# pulse_generator.net
KiCad netlist of a schematic drawn in EAGLE
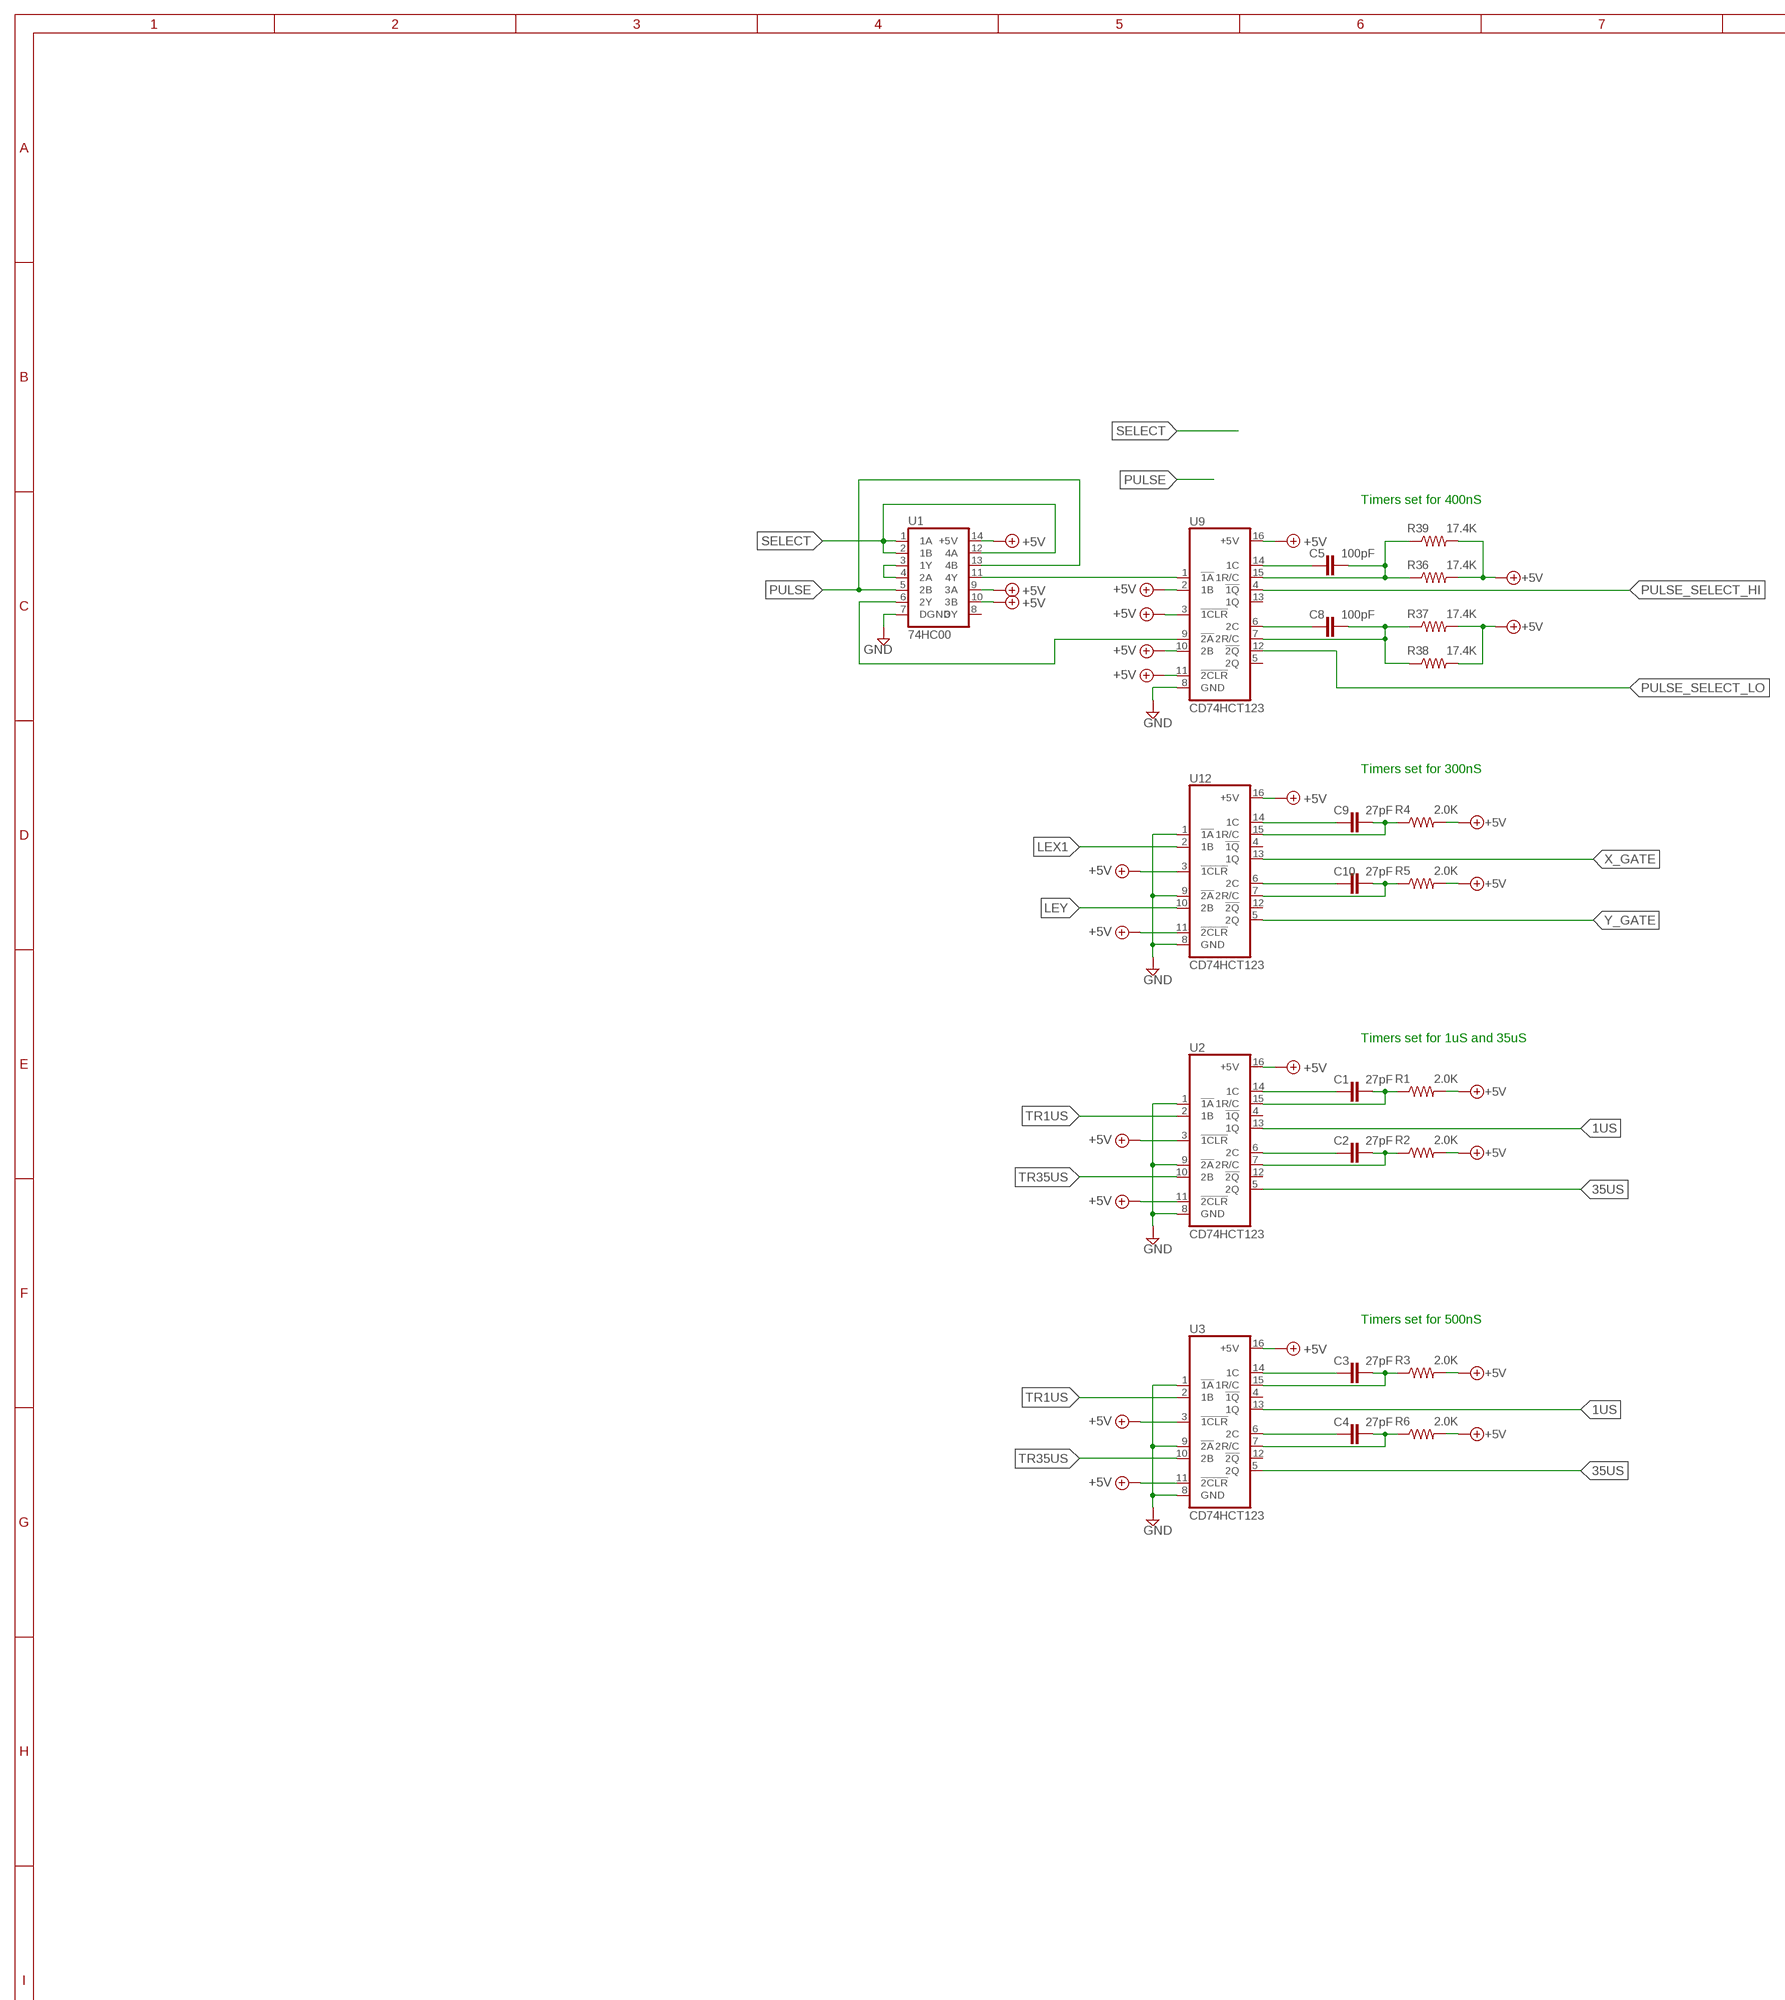
[diagram p0: schematic, sheet 1, part 1 of 2]
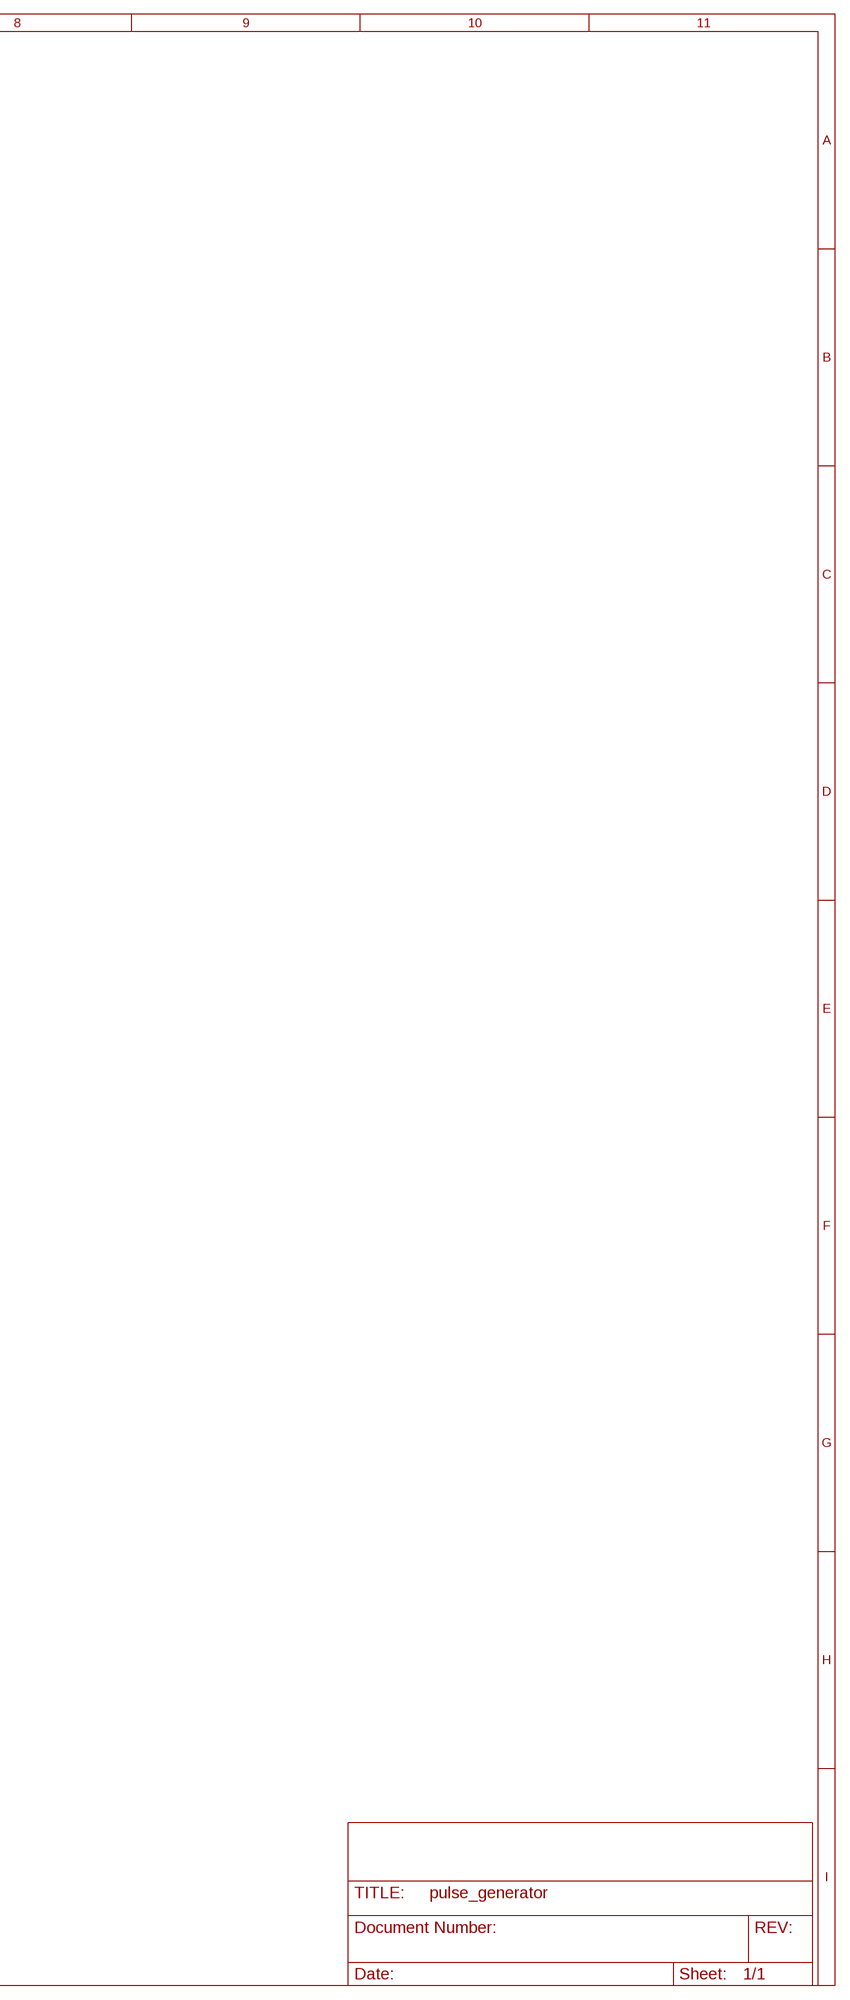
[diagram p1: schematic, sheet 1, part 2 of 2]

(export (version "E")
  (design (tool "Eeschema 10.0.6"))
  (components
    (comp (ref "C1")
      (value "27pF")
      (footprint "eagle-import:C2.5")
      (libsource (lib "eagle-import") (part "C-0.1"))
    )
    (comp (ref "C2")
      (value "27pF")
      (footprint "eagle-import:C2.5")
      (libsource (lib "eagle-import") (part "C-0.1"))
    )
    (comp (ref "C3")
      (value "27pF")
      (footprint "eagle-import:C2.5")
      (libsource (lib "eagle-import") (part "C-0.1"))
    )
    (comp (ref "C4")
      (value "27pF")
      (footprint "eagle-import:C2.5")
      (libsource (lib "eagle-import") (part "C-0.1"))
    )
    (comp (ref "C5")
      (value "100pF")
      (footprint "eagle-import:C2.5")
      (libsource (lib "eagle-import") (part "C-0.1"))
    )
    (comp (ref "C8")
      (value "100pF")
      (footprint "eagle-import:C2.5")
      (libsource (lib "eagle-import") (part "C-0.1"))
    )
    (comp (ref "C9")
      (value "27pF")
      (footprint "eagle-import:C2.5")
      (libsource (lib "eagle-import") (part "C-0.1"))
    )
    (comp (ref "C10")
      (value "27pF")
      (footprint "eagle-import:C2.5")
      (libsource (lib "eagle-import") (part "C-0.1"))
    )
    (comp (ref "R1")
      (value "2.0K")
      (footprint "eagle-import:0207_10")
      (libsource (lib "eagle-import") (part "R-1/4WATT"))
    )
    (comp (ref "R2")
      (value "2.0K")
      (footprint "eagle-import:0207_10")
      (libsource (lib "eagle-import") (part "R-1/4WATT"))
    )
    (comp (ref "R3")
      (value "2.0K")
      (footprint "eagle-import:0207_10")
      (libsource (lib "eagle-import") (part "R-1/4WATT"))
    )
    (comp (ref "R4")
      (value "2.0K")
      (footprint "eagle-import:0207_10")
      (libsource (lib "eagle-import") (part "R-1/4WATT"))
    )
    (comp (ref "R5")
      (value "2.0K")
      (footprint "eagle-import:0207_10")
      (libsource (lib "eagle-import") (part "R-1/4WATT"))
    )
    (comp (ref "R6")
      (value "2.0K")
      (footprint "eagle-import:0207_10")
      (libsource (lib "eagle-import") (part "R-1/4WATT"))
    )
    (comp (ref "R36")
      (value "17.4K")
      (footprint "eagle-import:0207_10")
      (libsource (lib "eagle-import") (part "R-1/4WATT"))
    )
    (comp (ref "R37")
      (value "17.4K")
      (footprint "eagle-import:0207_10")
      (libsource (lib "eagle-import") (part "R-1/4WATT"))
    )
    (comp (ref "R38")
      (value "17.4K")
      (footprint "eagle-import:0207_10")
      (libsource (lib "eagle-import") (part "R-1/4WATT"))
    )
    (comp (ref "R39")
      (value "17.4K")
      (footprint "eagle-import:0207_10")
      (libsource (lib "eagle-import") (part "R-1/4WATT"))
    )
    (comp (ref "U1")
      (value "74HC00")
      (footprint "eagle-import:DIP-14")
      (libsource (lib "eagle-import") (part "CD74HC00"))
    )
    (comp (ref "U2")
      (value "CD74HCT123")
      (footprint "eagle-import:DIP-16")
      (libsource (lib "eagle-import") (part "CD74HCT123"))
    )
    (comp (ref "U3")
      (value "CD74HCT123")
      (footprint "eagle-import:DIP-16")
      (libsource (lib "eagle-import") (part "CD74HCT123"))
    )
    (comp (ref "U9")
      (value "CD74HCT123")
      (footprint "eagle-import:DIP-16")
      (libsource (lib "eagle-import") (part "CD74HCT123"))
    )
    (comp (ref "U12")
      (value "CD74HCT123")
      (footprint "eagle-import:DIP-16")
      (libsource (lib "eagle-import") (part "CD74HCT123"))
    )
  )
  (nets
    (net (code "1") (name "+5V") (class "Default")
      (node (ref "R1") (pin "2") (pinfunction "P$2_2") (pintype "passive"))
      (node (ref "R2") (pin "2") (pinfunction "P$2_2") (pintype "passive"))
      (node (ref "R3") (pin "2") (pinfunction "P$2_2") (pintype "passive"))
      (node (ref "R36") (pin "2") (pinfunction "P$2_2") (pintype "passive"))
      (node (ref "R37") (pin "2") (pinfunction "P$2_2") (pintype "passive"))
      (node (ref "R38") (pin "2") (pinfunction "P$2_2") (pintype "passive"))
      (node (ref "R39") (pin "2") (pinfunction "P$2_2") (pintype "passive"))
      (node (ref "R4") (pin "2") (pinfunction "P$2_2") (pintype "passive"))
      (node (ref "R5") (pin "2") (pinfunction "P$2_2") (pintype "passive"))
      (node (ref "R6") (pin "2") (pinfunction "P$2_2") (pintype "passive"))
      (node (ref "U1") (pin "10") (pinfunction "3B_10") (pintype "input"))
      (node (ref "U1") (pin "14") (pinfunction "+5V_14") (pintype "power_in"))
      (node (ref "U1") (pin "9") (pinfunction "3A_9") (pintype "input"))
      (node (ref "U12") (pin "11") (pinfunction "~{2CLR}_11") (pintype "input"))
      (node (ref "U12") (pin "16") (pinfunction "+5V_16") (pintype "power_in"))
      (node (ref "U12") (pin "3") (pinfunction "~{1CLR}_3") (pintype "input"))
      (node (ref "U2") (pin "11") (pinfunction "~{2CLR}_11") (pintype "input"))
      (node (ref "U2") (pin "16") (pinfunction "+5V_16") (pintype "power_in"))
      (node (ref "U2") (pin "3") (pinfunction "~{1CLR}_3") (pintype "input"))
      (node (ref "U3") (pin "11") (pinfunction "~{2CLR}_11") (pintype "input"))
      (node (ref "U3") (pin "16") (pinfunction "+5V_16") (pintype "power_in"))
      (node (ref "U3") (pin "3") (pinfunction "~{1CLR}_3") (pintype "input"))
      (node (ref "U9") (pin "10") (pinfunction "2B_10") (pintype "input"))
      (node (ref "U9") (pin "11") (pinfunction "~{2CLR}_11") (pintype "input"))
      (node (ref "U9") (pin "16") (pinfunction "+5V_16") (pintype "power_in"))
      (node (ref "U9") (pin "2") (pinfunction "1B_2") (pintype "input"))
      (node (ref "U9") (pin "3") (pinfunction "~{1CLR}_3") (pintype "input"))
    )
    (net (code "2") (name "1US") (class "Default")
      (node (ref "U2") (pin "13") (pinfunction "1Q_13") (pintype "output"))
      (node (ref "U3") (pin "13") (pinfunction "1Q_13") (pintype "output"))
    )
    (net (code "3") (name "35US") (class "Default")
      (node (ref "U2") (pin "5") (pinfunction "2Q_5") (pintype "output"))
      (node (ref "U3") (pin "5") (pinfunction "2Q_5") (pintype "output"))
    )
    (net (code "4") (name "GND") (class "Default")
      (node (ref "U1") (pin "7") (pinfunction "DGND_7") (pintype "power_in"))
      (node (ref "U12") (pin "1") (pinfunction "~{1A}_1") (pintype "input"))
      (node (ref "U12") (pin "8") (pinfunction "GND_8") (pintype "power_in"))
      (node (ref "U12") (pin "9") (pinfunction "~{2A}_9") (pintype "input"))
      (node (ref "U2") (pin "1") (pinfunction "~{1A}_1") (pintype "input"))
      (node (ref "U2") (pin "8") (pinfunction "GND_8") (pintype "power_in"))
      (node (ref "U2") (pin "9") (pinfunction "~{2A}_9") (pintype "input"))
      (node (ref "U3") (pin "1") (pinfunction "~{1A}_1") (pintype "input"))
      (node (ref "U3") (pin "8") (pinfunction "GND_8") (pintype "power_in"))
      (node (ref "U3") (pin "9") (pinfunction "~{2A}_9") (pintype "input"))
      (node (ref "U9") (pin "8") (pinfunction "GND_8") (pintype "power_in"))
    )
    (net (code "5") (name "LEX1") (class "Default")
      (node (ref "U12") (pin "2") (pinfunction "1B_2") (pintype "input"))
    )
    (net (code "7") (name "Net-(R1-P$1)") (class "Default")
      (node (ref "C1") (pin "2") (pinfunction "2_2") (pintype "passive"))
      (node (ref "R1") (pin "1") (pinfunction "P$1_1") (pintype "passive"))
      (node (ref "U2") (pin "15") (pinfunction "1R/C_15") (pintype "passive"))
    )
    (net (code "8") (name "Net-(R2-P$1)") (class "Default")
      (node (ref "C2") (pin "2") (pinfunction "2_2") (pintype "passive"))
      (node (ref "R2") (pin "1") (pinfunction "P$1_1") (pintype "passive"))
      (node (ref "U2") (pin "7") (pinfunction "2R/C_7") (pintype "passive"))
    )
    (net (code "9") (name "Net-(R3-P$1)") (class "Default")
      (node (ref "C3") (pin "2") (pinfunction "2_2") (pintype "passive"))
      (node (ref "R3") (pin "1") (pinfunction "P$1_1") (pintype "passive"))
      (node (ref "U3") (pin "15") (pinfunction "1R/C_15") (pintype "passive"))
    )
    (net (code "10") (name "Net-(R4-P$1)") (class "Default")
      (node (ref "C9") (pin "2") (pinfunction "2_2") (pintype "passive"))
      (node (ref "R4") (pin "1") (pinfunction "P$1_1") (pintype "passive"))
      (node (ref "U12") (pin "15") (pinfunction "1R/C_15") (pintype "passive"))
    )
    (net (code "11") (name "Net-(R5-P$1)") (class "Default")
      (node (ref "C10") (pin "2") (pinfunction "2_2") (pintype "passive"))
      (node (ref "R5") (pin "1") (pinfunction "P$1_1") (pintype "passive"))
      (node (ref "U12") (pin "7") (pinfunction "2R/C_7") (pintype "passive"))
    )
    (net (code "12") (name "Net-(R6-P$1)") (class "Default")
      (node (ref "C4") (pin "2") (pinfunction "2_2") (pintype "passive"))
      (node (ref "R6") (pin "1") (pinfunction "P$1_1") (pintype "passive"))
      (node (ref "U3") (pin "7") (pinfunction "2R/C_7") (pintype "passive"))
    )
    (net (code "13") (name "Net-(R36-P$1)") (class "Default")
      (node (ref "C5") (pin "2") (pinfunction "2_2") (pintype "passive"))
      (node (ref "R36") (pin "1") (pinfunction "P$1_1") (pintype "passive"))
      (node (ref "R39") (pin "1") (pinfunction "P$1_1") (pintype "passive"))
      (node (ref "U9") (pin "15") (pinfunction "1R/C_15") (pintype "passive"))
    )
    (net (code "14") (name "Net-(R37-P$1)") (class "Default")
      (node (ref "C8") (pin "2") (pinfunction "2_2") (pintype "passive"))
      (node (ref "R37") (pin "1") (pinfunction "P$1_1") (pintype "passive"))
      (node (ref "R38") (pin "1") (pinfunction "P$1_1") (pintype "passive"))
      (node (ref "U9") (pin "7") (pinfunction "2R/C_7") (pintype "passive"))
    )
    (net (code "15") (name "Net-(U1-1Y)") (class "Default")
      (node (ref "U1") (pin "3") (pinfunction "1Y_3") (pintype "output"))
      (node (ref "U1") (pin "4") (pinfunction "2A_4") (pintype "input"))
    )
    (net (code "16") (name "Net-(U1-2Y)") (class "Default")
      (node (ref "U1") (pin "6") (pinfunction "2Y_6") (pintype "output"))
      (node (ref "U9") (pin "9") (pinfunction "~{2A}_9") (pintype "input"))
    )
    (net (code "17") (name "Net-(U1-4Y)") (class "Default")
      (node (ref "U1") (pin "11") (pinfunction "4Y_11") (pintype "output"))
      (node (ref "U9") (pin "1") (pinfunction "~{1A}_1") (pintype "input"))
    )
    (net (code "18") (name "Net-(U2-1C)") (class "Default")
      (node (ref "C1") (pin "1") (pinfunction "1_1") (pintype "passive"))
      (node (ref "U2") (pin "14") (pinfunction "1C_14") (pintype "passive"))
    )
    (net (code "19") (name "Net-(U2-2C)") (class "Default")
      (node (ref "C2") (pin "1") (pinfunction "1_1") (pintype "passive"))
      (node (ref "U2") (pin "6") (pinfunction "2C_6") (pintype "passive"))
    )
    (net (code "20") (name "Net-(U3-1C)") (class "Default")
      (node (ref "C3") (pin "1") (pinfunction "1_1") (pintype "passive"))
      (node (ref "U3") (pin "14") (pinfunction "1C_14") (pintype "passive"))
    )
    (net (code "21") (name "Net-(U3-2C)") (class "Default")
      (node (ref "C4") (pin "1") (pinfunction "1_1") (pintype "passive"))
      (node (ref "U3") (pin "6") (pinfunction "2C_6") (pintype "passive"))
    )
    (net (code "22") (name "Net-(U9-1C)") (class "Default")
      (node (ref "C5") (pin "1") (pinfunction "1_1") (pintype "passive"))
      (node (ref "U9") (pin "14") (pinfunction "1C_14") (pintype "passive"))
    )
    (net (code "23") (name "Net-(U9-2C)") (class "Default")
      (node (ref "C8") (pin "1") (pinfunction "1_1") (pintype "passive"))
      (node (ref "U9") (pin "6") (pinfunction "2C_6") (pintype "passive"))
    )
    (net (code "24") (name "Net-(U12-1C)") (class "Default")
      (node (ref "C9") (pin "1") (pinfunction "1_1") (pintype "passive"))
      (node (ref "U12") (pin "14") (pinfunction "1C_14") (pintype "passive"))
    )
    (net (code "25") (name "Net-(U12-2C)") (class "Default")
      (node (ref "C10") (pin "1") (pinfunction "1_1") (pintype "passive"))
      (node (ref "U12") (pin "6") (pinfunction "2C_6") (pintype "passive"))
    )
    (net (code "26") (name "PULSE") (class "Default")
      (node (ref "U1") (pin "13") (pinfunction "4B_13") (pintype "input"))
      (node (ref "U1") (pin "5") (pinfunction "2B_5") (pintype "input"))
    )
    (net (code "27") (name "PULSE_SELECT_HI") (class "Default")
      (node (ref "U9") (pin "4") (pinfunction "~{1Q}_4") (pintype "output"))
    )
    (net (code "28") (name "PULSE_SELECT_LO") (class "Default")
      (node (ref "U9") (pin "12") (pinfunction "~{2Q}_12") (pintype "output"))
    )
    (net (code "29") (name "SELECT") (class "Default")
      (node (ref "U1") (pin "1") (pinfunction "1A_1") (pintype "input"))
      (node (ref "U1") (pin "12") (pinfunction "4A_12") (pintype "input"))
      (node (ref "U1") (pin "2") (pinfunction "1B_2") (pintype "input"))
    )
    (net (code "30") (name "TR1US") (class "Default")
      (node (ref "U2") (pin "2") (pinfunction "1B_2") (pintype "input"))
      (node (ref "U3") (pin "2") (pinfunction "1B_2") (pintype "input"))
    )
    (net (code "31") (name "TR35US") (class "Default")
      (node (ref "U2") (pin "10") (pinfunction "2B_10") (pintype "input"))
      (node (ref "U3") (pin "10") (pinfunction "2B_10") (pintype "input"))
    )
    (net (code "32") (name "X_GATE") (class "Default")
      (node (ref "U12") (pin "13") (pinfunction "1Q_13") (pintype "output"))
    )
    (net (code "33") (name "Y_GATE") (class "Default")
      (node (ref "U12") (pin "5") (pinfunction "2Q_5") (pintype "output"))
    )
    (net (code "34") (name "unconnected-(U1-3Y-Pad8)") (class "Default")
      (node (ref "U1") (pin "8") (pinfunction "3Y_8") (pintype "output"))
    )
    (net (code "35") (name "unconnected-(U2-~{1Q}-Pad4)") (class "Default")
      (node (ref "U2") (pin "4") (pinfunction "~{1Q}_4") (pintype "output"))
    )
    (net (code "36") (name "unconnected-(U2-~{2Q}-Pad12)") (class "Default")
      (node (ref "U2") (pin "12") (pinfunction "~{2Q}_12") (pintype "output"))
    )
    (net (code "37") (name "unconnected-(U3-~{1Q}-Pad4)") (class "Default")
      (node (ref "U3") (pin "4") (pinfunction "~{1Q}_4") (pintype "output"))
    )
    (net (code "38") (name "unconnected-(U3-~{2Q}-Pad12)") (class "Default")
      (node (ref "U3") (pin "12") (pinfunction "~{2Q}_12") (pintype "output"))
    )
    (net (code "39") (name "unconnected-(U9-1Q-Pad13)") (class "Default")
      (node (ref "U9") (pin "13") (pinfunction "1Q_13") (pintype "output"))
    )
    (net (code "40") (name "unconnected-(U9-2Q-Pad5)") (class "Default")
      (node (ref "U9") (pin "5") (pinfunction "2Q_5") (pintype "output"))
    )
    (net (code "41") (name "unconnected-(U12-2B-Pad10)") (class "Default")
      (node (ref "U12") (pin "10") (pinfunction "2B_10") (pintype "input"))
    )
    (net (code "42") (name "unconnected-(U12-~{1Q}-Pad4)") (class "Default")
      (node (ref "U12") (pin "4") (pinfunction "~{1Q}_4") (pintype "output"))
    )
    (net (code "43") (name "unconnected-(U12-~{2Q}-Pad12)") (class "Default")
      (node (ref "U12") (pin "12") (pinfunction "~{2Q}_12") (pintype "output"))
    )
  )
)
